# io_dac_convert.net
KiCad netlist of a schematic drawn in EAGLE
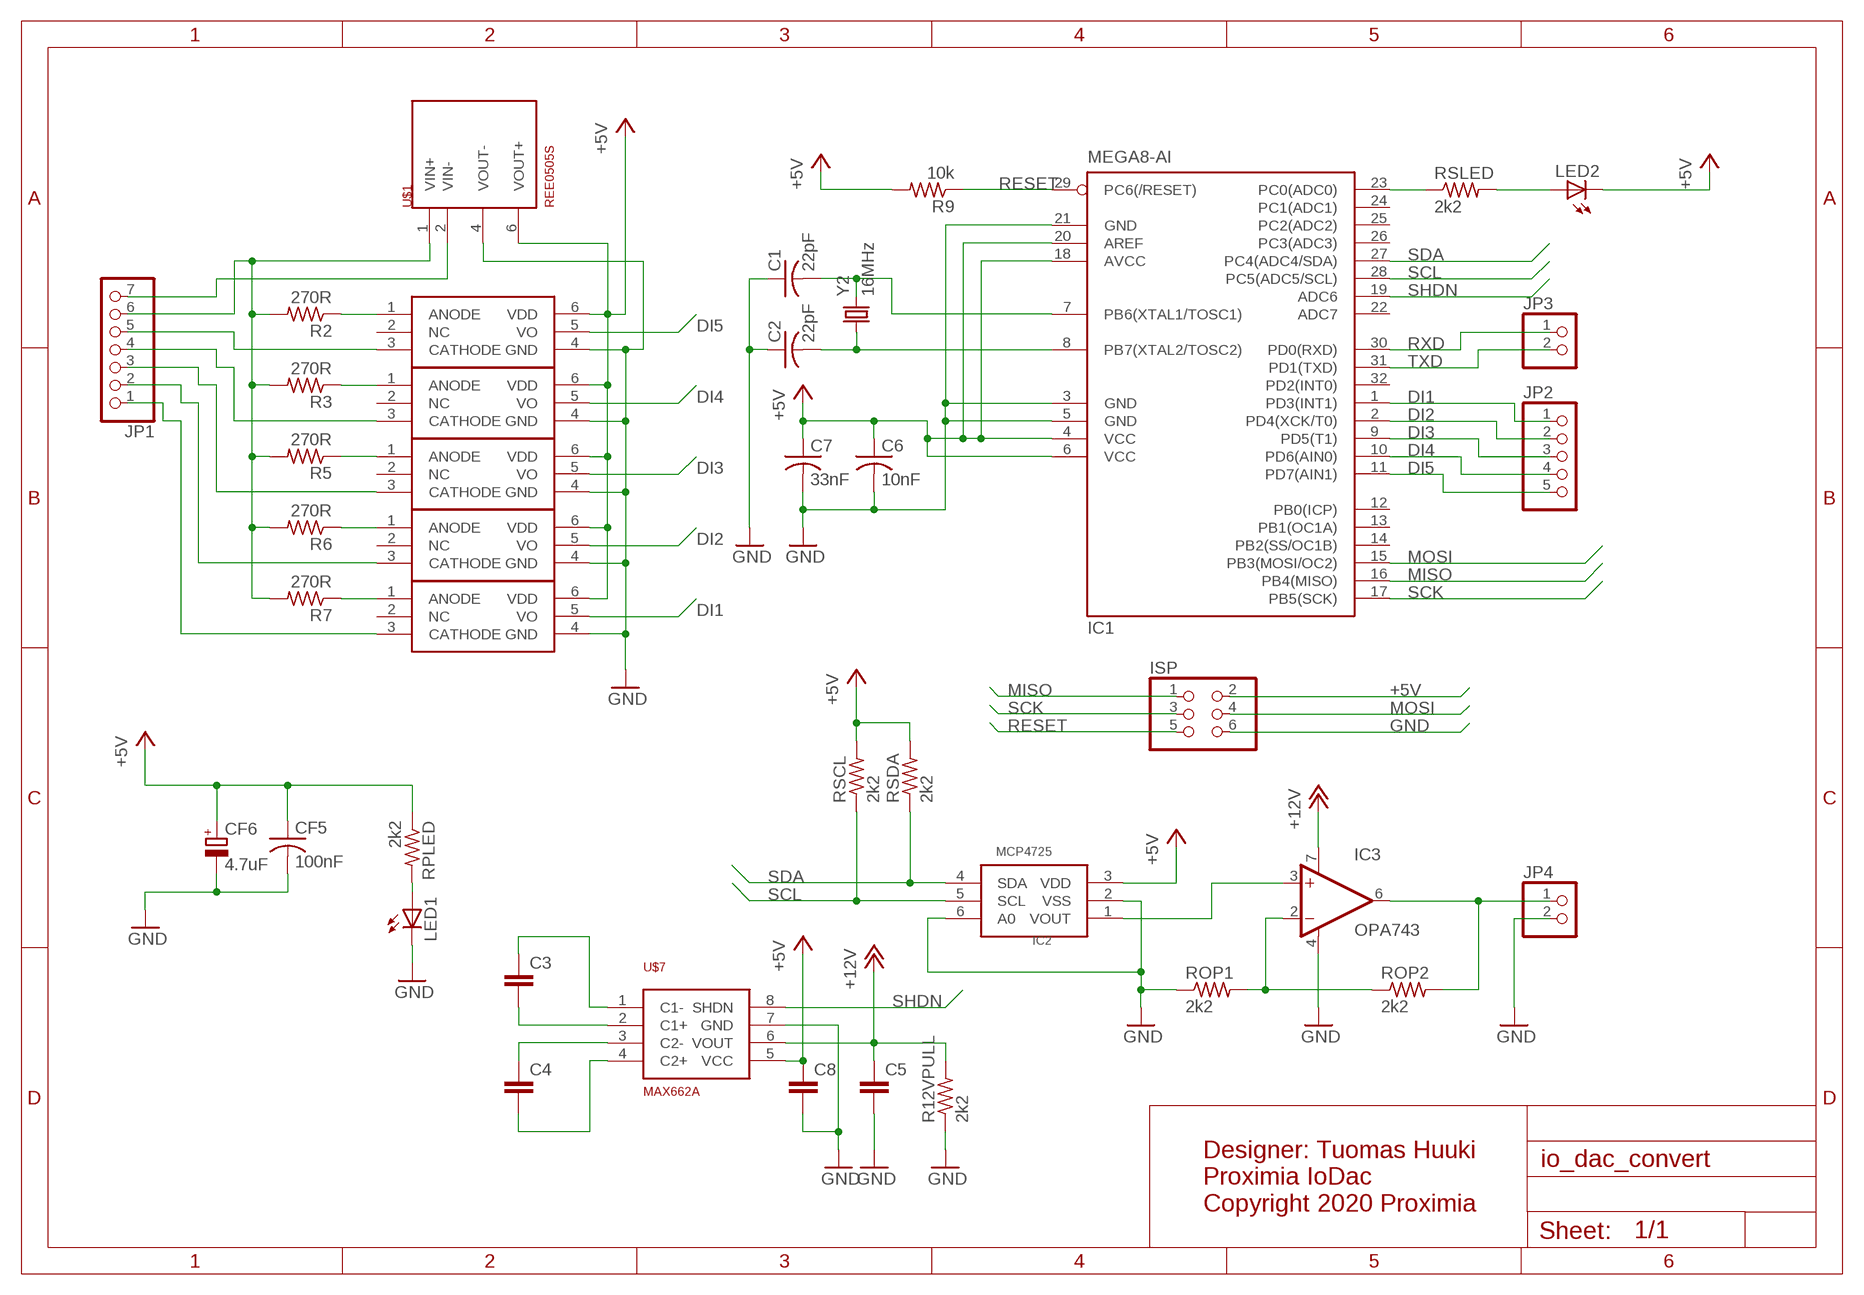
[diagram p0: schematic, sheet 1]

(export (version "E")
  (design (tool "Eeschema 10.0.6"))
  (components
    (comp (ref "C1")
      (value "22pF")
      (footprint "eagle-import:C0603")
      (libsource (lib "eagle-import") (part "C-USC0603"))
    )
    (comp (ref "C2")
      (value "22pF")
      (footprint "eagle-import:C0603")
      (libsource (lib "eagle-import") (part "C-USC0603"))
    )
    (comp (ref "C3")
      (value "C-EUC1206")
      (footprint "eagle-import:C1206")
      (libsource (lib "eagle-import") (part "C-EUC1206"))
    )
    (comp (ref "C4")
      (value "C-EUC1206")
      (footprint "eagle-import:C1206")
      (libsource (lib "eagle-import") (part "C-EUC1206"))
    )
    (comp (ref "C5")
      (value "C-EUC1206")
      (footprint "eagle-import:C1206")
      (libsource (lib "eagle-import") (part "C-EUC1206"))
    )
    (comp (ref "C6")
      (value "10nF")
      (footprint "eagle-import:C0603")
      (libsource (lib "eagle-import") (part "resistor_C-USC0603"))
    )
    (comp (ref "C7")
      (value "33nF")
      (footprint "eagle-import:C0603")
      (libsource (lib "eagle-import") (part "resistor_C-USC0603"))
    )
    (comp (ref "C8")
      (value "C-EUC1206")
      (footprint "eagle-import:C1206")
      (libsource (lib "eagle-import") (part "C-EUC1206"))
    )
    (comp (ref "CF5")
      (value "100nF")
      (footprint "eagle-import:C0603")
      (libsource (lib "eagle-import") (part "C-USC0603"))
    )
    (comp (ref "CF6")
      (value "4.7uF")
      (footprint "eagle-import:PANASONIC_B")
      (libsource (lib "eagle-import") (part "CPOL-EUB"))
    )
    (comp (ref "IC1")
      (value "MEGA8-AI")
      (footprint "eagle-import:TQFP32-08")
      (fields (field (name "MPN") "ATMEGA8-16AU"))
      (libsource (lib "eagle-import") (part "MEGA8-AI"))
    )
    (comp (ref "IC2")
      (value "MCP4725")
      (footprint "eagle-import:SOT23-6")
      (libsource (lib "eagle-import") (part "MCP4725"))
    )
    (comp (ref "IC3")
      (value "OPA743")
      (footprint "eagle-import:SO08")
      (fields (field (name "MPN") "AD8001ARZ"))
      (libsource (lib "eagle-import") (part "OPA658U"))
    )
    (comp (ref "ISP")
      (value "PINHD-2X3")
      (footprint "eagle-import:2X03")
      (libsource (lib "eagle-import") (part "PINHD-2X3"))
    )
    (comp (ref "JP1")
      (value "PINHD-1X7")
      (footprint "eagle-import:1X07")
      (libsource (lib "eagle-import") (part "PINHD-1X7"))
    )
    (comp (ref "JP2")
      (value "PINHD-1X5")
      (footprint "eagle-import:1X05")
      (libsource (lib "eagle-import") (part "PINHD-1X5"))
    )
    (comp (ref "JP3")
      (value "PINHD-1X2")
      (footprint "eagle-import:1X02")
      (libsource (lib "eagle-import") (part "PINHD-1X2"))
    )
    (comp (ref "JP4")
      (value "PINHD-1X2")
      (footprint "eagle-import:1X02")
      (libsource (lib "eagle-import") (part "PINHD-1X2"))
    )
    (comp (ref "LED1")
      (value "LEDSML1206")
      (footprint "eagle-import:SML1206")
      (libsource (lib "eagle-import") (part "LEDSML1206"))
    )
    (comp (ref "LED2")
      (value "LEDSML1206")
      (footprint "eagle-import:SML1206")
      (libsource (lib "eagle-import") (part "LEDSML1206"))
    )
    (comp (ref "R2")
      (value "270R")
      (footprint "eagle-import:R0603")
      (libsource (lib "eagle-import") (part "R-US_R0603"))
    )
    (comp (ref "R3")
      (value "270R")
      (footprint "eagle-import:R0603")
      (libsource (lib "eagle-import") (part "R-US_R0603"))
    )
    (comp (ref "R5")
      (value "270R")
      (footprint "eagle-import:R0603")
      (libsource (lib "eagle-import") (part "R-US_R0603"))
    )
    (comp (ref "R6")
      (value "270R")
      (footprint "eagle-import:R0603")
      (libsource (lib "eagle-import") (part "R-US_R0603"))
    )
    (comp (ref "R7")
      (value "270R")
      (footprint "eagle-import:R0603")
      (libsource (lib "eagle-import") (part "R-US_R0603"))
    )
    (comp (ref "R9")
      (value "10k")
      (footprint "eagle-import:R0603")
      (libsource (lib "eagle-import") (part "resistor_R-US_R0603"))
    )
    (comp (ref "R12VPULL")
      (value "2k2")
      (footprint "eagle-import:R0603")
      (libsource (lib "eagle-import") (part "R-US_R0603"))
    )
    (comp (ref "ROP1")
      (value "2k2")
      (footprint "eagle-import:R0603")
      (libsource (lib "eagle-import") (part "R-US_R0603"))
    )
    (comp (ref "ROP2")
      (value "2k2")
      (footprint "eagle-import:R0603")
      (libsource (lib "eagle-import") (part "R-US_R0603"))
    )
    (comp (ref "RPLED")
      (value "2k2")
      (footprint "eagle-import:R0603")
      (libsource (lib "eagle-import") (part "R-US_R0603"))
    )
    (comp (ref "RSCL")
      (value "2k2")
      (footprint "eagle-import:R0603")
      (libsource (lib "eagle-import") (part "R-US_R0603"))
    )
    (comp (ref "RSDA")
      (value "2k2")
      (footprint "eagle-import:R0603")
      (libsource (lib "eagle-import") (part "R-US_R0603"))
    )
    (comp (ref "RSLED")
      (value "2k2")
      (footprint "eagle-import:R0603")
      (libsource (lib "eagle-import") (part "R-US_R0603"))
    )
    (comp (ref "U$1")
      (value "REE0505S")
      (footprint "eagle-import:SIP-6")
      (libsource (lib "eagle-import") (part "REE0505S"))
    )
    (comp (ref "U$2")
      (value "SI8710")
      (footprint "eagle-import:SDIP-6")
      (libsource (lib "eagle-import") (part "SI8710"))
    )
    (comp (ref "U$3")
      (value "SI8710")
      (footprint "eagle-import:SDIP-6")
      (libsource (lib "eagle-import") (part "SI8710"))
    )
    (comp (ref "U$4")
      (value "SI8710")
      (footprint "eagle-import:SDIP-6")
      (libsource (lib "eagle-import") (part "SI8710"))
    )
    (comp (ref "U$5")
      (value "SI8710")
      (footprint "eagle-import:SDIP-6")
      (libsource (lib "eagle-import") (part "SI8710"))
    )
    (comp (ref "U$6")
      (value "SI8710")
      (footprint "eagle-import:SDIP-6")
      (libsource (lib "eagle-import") (part "SI8710"))
    )
    (comp (ref "U$7")
      (value "MAX662A")
      (footprint "eagle-import:SO8")
      (libsource (lib "eagle-import") (part "MAX662A"))
    )
    (comp (ref "Y2")
      (value "16MHz")
      (footprint "eagle-import:CRYSTAL-SMD-5X3")
      (libsource (lib "eagle-import") (part "CRYSTAL5X3"))
    )
  )
  (nets
    (net (code "1") (name "+5V") (class "Default")
      (node (ref "C6") (pin "1") (pinfunction "1_1") (pintype "passive"))
      (node (ref "C7") (pin "1") (pinfunction "1_1") (pintype "passive"))
      (node (ref "C8") (pin "1") (pinfunction "1_1") (pintype "passive"))
      (node (ref "CF5") (pin "1") (pinfunction "1_1") (pintype "passive"))
      (node (ref "CF6") (pin "+") (pinfunction "+_+") (pintype "passive"))
      (node (ref "IC1") (pin "18") (pinfunction "AVCC_18") (pintype "power_in"))
      (node (ref "IC1") (pin "20") (pinfunction "AREF_20") (pintype "passive"))
      (node (ref "IC1") (pin "4") (pinfunction "VCC_4") (pintype "power_in"))
      (node (ref "IC1") (pin "6") (pinfunction "VCC_6") (pintype "power_in"))
      (node (ref "IC2") (pin "3") (pinfunction "VDD_3") (pintype "bidirectional"))
      (node (ref "ISP") (pin "2") (pinfunction "2_2") (pintype "passive"))
      (node (ref "LED2") (pin "C") (pinfunction "C_C") (pintype "passive"))
      (node (ref "R9") (pin "2") (pinfunction "2_2") (pintype "passive"))
      (node (ref "RPLED") (pin "1") (pinfunction "1_1") (pintype "passive"))
      (node (ref "RSCL") (pin "2") (pinfunction "2_2") (pintype "passive"))
      (node (ref "RSDA") (pin "2") (pinfunction "2_2") (pintype "passive"))
      (node (ref "U$1") (pin "6") (pinfunction "VOUT+_6") (pintype "bidirectional"))
      (node (ref "U$2") (pin "6") (pinfunction "VDD_6") (pintype "bidirectional"))
      (node (ref "U$3") (pin "6") (pinfunction "VDD_6") (pintype "bidirectional"))
      (node (ref "U$4") (pin "6") (pinfunction "VDD_6") (pintype "bidirectional"))
      (node (ref "U$5") (pin "6") (pinfunction "VDD_6") (pintype "bidirectional"))
      (node (ref "U$6") (pin "6") (pinfunction "VDD_6") (pintype "bidirectional"))
      (node (ref "U$7") (pin "5") (pinfunction "VCC_5") (pintype "bidirectional"))
    )
    (net (code "2") (name "+12V") (class "Default")
      (node (ref "C5") (pin "1") (pinfunction "1_1") (pintype "passive"))
      (node (ref "IC3") (pin "7") (pinfunction "V+_7") (pintype "power_in"))
      (node (ref "R12VPULL") (pin "2") (pinfunction "2_2") (pintype "passive"))
      (node (ref "U$7") (pin "6") (pinfunction "VOUT_6") (pintype "bidirectional"))
    )
    (net (code "3") (name "/DI1") (class "Default")
      (node (ref "IC1") (pin "1") (pinfunction "PD3(INT1)_1") (pintype "bidirectional"))
      (node (ref "JP2") (pin "1") (pinfunction "1_1") (pintype "passive"))
      (node (ref "U$6") (pin "5") (pinfunction "VO_5") (pintype "bidirectional"))
    )
    (net (code "4") (name "/DI2") (class "Default")
      (node (ref "IC1") (pin "2") (pinfunction "PD4(XCK/T0)_2") (pintype "bidirectional"))
      (node (ref "JP2") (pin "2") (pinfunction "2_2") (pintype "passive"))
      (node (ref "U$5") (pin "5") (pinfunction "VO_5") (pintype "bidirectional"))
    )
    (net (code "5") (name "/DI3") (class "Default")
      (node (ref "IC1") (pin "9") (pinfunction "PD5(T1)_9") (pintype "bidirectional"))
      (node (ref "JP2") (pin "3") (pinfunction "3_3") (pintype "passive"))
      (node (ref "U$4") (pin "5") (pinfunction "VO_5") (pintype "bidirectional"))
    )
    (net (code "6") (name "/DI4") (class "Default")
      (node (ref "IC1") (pin "10") (pinfunction "PD6(AIN0)_10") (pintype "bidirectional"))
      (node (ref "JP2") (pin "4") (pinfunction "4_4") (pintype "passive"))
      (node (ref "U$3") (pin "5") (pinfunction "VO_5") (pintype "bidirectional"))
    )
    (net (code "7") (name "/DI5") (class "Default")
      (node (ref "IC1") (pin "11") (pinfunction "PD7(AIN1)_11") (pintype "bidirectional"))
      (node (ref "JP2") (pin "5") (pinfunction "5_5") (pintype "passive"))
      (node (ref "U$2") (pin "5") (pinfunction "VO_5") (pintype "bidirectional"))
    )
    (net (code "8") (name "/MISO") (class "Default")
      (node (ref "IC1") (pin "16") (pinfunction "PB4(MISO)_16") (pintype "bidirectional"))
      (node (ref "ISP") (pin "1") (pinfunction "1_1") (pintype "passive"))
    )
    (net (code "9") (name "/MOSI") (class "Default")
      (node (ref "IC1") (pin "15") (pinfunction "PB3(MOSI/OC2)_15") (pintype "bidirectional"))
      (node (ref "ISP") (pin "4") (pinfunction "4_4") (pintype "passive"))
    )
    (net (code "10") (name "/RESET") (class "Default")
      (node (ref "IC1") (pin "29") (pinfunction "PC6(/RESET)_29") (pintype "bidirectional"))
      (node (ref "ISP") (pin "5") (pinfunction "5_5") (pintype "passive"))
      (node (ref "R9") (pin "1") (pinfunction "1_1") (pintype "passive"))
    )
    (net (code "11") (name "/RXD") (class "Default")
      (node (ref "IC1") (pin "30") (pinfunction "PD0(RXD)_30") (pintype "bidirectional"))
      (node (ref "JP3") (pin "1") (pinfunction "1_1") (pintype "passive"))
    )
    (net (code "12") (name "/SCK") (class "Default")
      (node (ref "IC1") (pin "17") (pinfunction "PB5(SCK)_17") (pintype "bidirectional"))
      (node (ref "ISP") (pin "3") (pinfunction "3_3") (pintype "passive"))
    )
    (net (code "13") (name "/SCL") (class "Default")
      (node (ref "IC1") (pin "28") (pinfunction "PC5(ADC5/SCL)_28") (pintype "bidirectional"))
      (node (ref "IC2") (pin "5") (pinfunction "SCL_5") (pintype "bidirectional"))
      (node (ref "RSCL") (pin "1") (pinfunction "1_1") (pintype "passive"))
    )
    (net (code "14") (name "/SDA") (class "Default")
      (node (ref "IC1") (pin "27") (pinfunction "PC4(ADC4/SDA)_27") (pintype "bidirectional"))
      (node (ref "IC2") (pin "4") (pinfunction "SDA_4") (pintype "bidirectional"))
      (node (ref "RSDA") (pin "1") (pinfunction "1_1") (pintype "passive"))
    )
    (net (code "15") (name "/SHDN") (class "Default")
      (node (ref "IC1") (pin "19") (pinfunction "ADC6_19") (pintype "bidirectional"))
      (node (ref "U$7") (pin "8") (pinfunction "SHDN_8") (pintype "bidirectional"))
    )
    (net (code "16") (name "/TXD") (class "Default")
      (node (ref "IC1") (pin "31") (pinfunction "PD1(TXD)_31") (pintype "bidirectional"))
      (node (ref "JP3") (pin "2") (pinfunction "2_2") (pintype "passive"))
    )
    (net (code "17") (name "GND") (class "Default")
      (node (ref "C1") (pin "1") (pinfunction "1_1") (pintype "passive"))
      (node (ref "C2") (pin "1") (pinfunction "1_1") (pintype "passive"))
      (node (ref "C5") (pin "2") (pinfunction "2_2") (pintype "passive"))
      (node (ref "C6") (pin "2") (pinfunction "2_2") (pintype "passive"))
      (node (ref "C7") (pin "2") (pinfunction "2_2") (pintype "passive"))
      (node (ref "C8") (pin "2") (pinfunction "2_2") (pintype "passive"))
      (node (ref "CF5") (pin "2") (pinfunction "2_2") (pintype "passive"))
      (node (ref "CF6") (pin "-") (pinfunction "-_-") (pintype "passive"))
      (node (ref "IC1") (pin "21") (pinfunction "GND_21") (pintype "power_in"))
      (node (ref "IC1") (pin "3") (pinfunction "GND_3") (pintype "power_in"))
      (node (ref "IC1") (pin "5") (pinfunction "GND_5") (pintype "power_in"))
      (node (ref "IC2") (pin "2") (pinfunction "VSS_2") (pintype "bidirectional"))
      (node (ref "IC2") (pin "6") (pinfunction "A0_6") (pintype "bidirectional"))
      (node (ref "IC3") (pin "4") (pinfunction "V-_4") (pintype "power_in"))
      (node (ref "ISP") (pin "6") (pinfunction "6_6") (pintype "passive"))
      (node (ref "JP4") (pin "2") (pinfunction "2_2") (pintype "passive"))
      (node (ref "LED1") (pin "C") (pinfunction "C_C") (pintype "passive"))
      (node (ref "R12VPULL") (pin "1") (pinfunction "1_1") (pintype "passive"))
      (node (ref "ROP1") (pin "1") (pinfunction "1_1") (pintype "passive"))
      (node (ref "U$1") (pin "4") (pinfunction "VOUT-_4") (pintype "bidirectional"))
      (node (ref "U$2") (pin "4") (pinfunction "GND_4") (pintype "bidirectional"))
      (node (ref "U$3") (pin "4") (pinfunction "GND_4") (pintype "bidirectional"))
      (node (ref "U$4") (pin "4") (pinfunction "GND_4") (pintype "bidirectional"))
      (node (ref "U$5") (pin "4") (pinfunction "GND_4") (pintype "bidirectional"))
      (node (ref "U$6") (pin "4") (pinfunction "GND_4") (pintype "bidirectional"))
      (node (ref "U$7") (pin "7") (pinfunction "GND_7") (pintype "bidirectional"))
    )
    (net (code "18") (name "Net-(IC1-PB6(XTAL1{slash}TOSC1))") (class "Default")
      (node (ref "C1") (pin "2") (pinfunction "2_2") (pintype "passive"))
      (node (ref "IC1") (pin "7") (pinfunction "PB6(XTAL1/TOSC1)_7") (pintype "bidirectional"))
      (node (ref "Y2") (pin "3") (pinfunction "2_3") (pintype "passive"))
    )
    (net (code "19") (name "Net-(IC1-PB7(XTAL2{slash}TOSC2))") (class "Default")
      (node (ref "C2") (pin "2") (pinfunction "2_2") (pintype "passive"))
      (node (ref "IC1") (pin "8") (pinfunction "PB7(XTAL2/TOSC2)_8") (pintype "bidirectional"))
      (node (ref "Y2") (pin "1") (pinfunction "1_1") (pintype "passive"))
    )
    (net (code "20") (name "Net-(IC1-PC0(ADC0))") (class "Default")
      (node (ref "IC1") (pin "23") (pinfunction "PC0(ADC0)_23") (pintype "bidirectional"))
      (node (ref "RSLED") (pin "1") (pinfunction "1_1") (pintype "passive"))
    )
    (net (code "21") (name "Net-(IC2-VOUT)") (class "Default")
      (node (ref "IC2") (pin "1") (pinfunction "VOUT_1") (pintype "bidirectional"))
      (node (ref "IC3") (pin "3") (pinfunction "+IN_3") (pintype "input"))
    )
    (net (code "22") (name "Net-(IC3--IN)") (class "Default")
      (node (ref "IC3") (pin "2") (pinfunction "-IN_2") (pintype "input"))
      (node (ref "ROP1") (pin "2") (pinfunction "2_2") (pintype "passive"))
      (node (ref "ROP2") (pin "1") (pinfunction "1_1") (pintype "passive"))
    )
    (net (code "23") (name "Net-(IC3-OUT)") (class "Default")
      (node (ref "IC3") (pin "6") (pinfunction "OUT_6") (pintype "output"))
      (node (ref "JP4") (pin "1") (pinfunction "1_1") (pintype "passive"))
      (node (ref "ROP2") (pin "2") (pinfunction "2_2") (pintype "passive"))
    )
    (net (code "24") (name "Net-(LED1-PadA)") (class "Default")
      (node (ref "LED1") (pin "A") (pinfunction "A_A") (pintype "passive"))
      (node (ref "RPLED") (pin "2") (pinfunction "2_2") (pintype "passive"))
    )
    (net (code "25") (name "Net-(LED2-PadA)") (class "Default")
      (node (ref "LED2") (pin "A") (pinfunction "A_A") (pintype "passive"))
      (node (ref "RSLED") (pin "2") (pinfunction "2_2") (pintype "passive"))
    )
    (net (code "26") (name "Net-(U$1-VIN+)") (class "Default")
      (node (ref "JP1") (pin "6") (pinfunction "6_6") (pintype "passive"))
      (node (ref "R2") (pin "2") (pinfunction "2_2") (pintype "passive"))
      (node (ref "R3") (pin "2") (pinfunction "2_2") (pintype "passive"))
      (node (ref "R5") (pin "2") (pinfunction "2_2") (pintype "passive"))
      (node (ref "R6") (pin "2") (pinfunction "2_2") (pintype "passive"))
      (node (ref "R7") (pin "2") (pinfunction "2_2") (pintype "passive"))
      (node (ref "U$1") (pin "1") (pinfunction "VIN+_1") (pintype "bidirectional"))
    )
    (net (code "27") (name "Net-(U$1-VIN-)") (class "Default")
      (node (ref "JP1") (pin "7") (pinfunction "7_7") (pintype "passive"))
      (node (ref "U$1") (pin "2") (pinfunction "VIN-_2") (pintype "bidirectional"))
    )
    (net (code "28") (name "Net-(U$2-ANODE)") (class "Default")
      (node (ref "R2") (pin "1") (pinfunction "1_1") (pintype "passive"))
      (node (ref "U$2") (pin "1") (pinfunction "ANODE_1") (pintype "bidirectional"))
    )
    (net (code "29") (name "Net-(U$2-CATHODE)") (class "Default")
      (node (ref "JP1") (pin "5") (pinfunction "5_5") (pintype "passive"))
      (node (ref "U$2") (pin "3") (pinfunction "CATHODE_3") (pintype "bidirectional"))
    )
    (net (code "30") (name "Net-(U$3-ANODE)") (class "Default")
      (node (ref "R3") (pin "1") (pinfunction "1_1") (pintype "passive"))
      (node (ref "U$3") (pin "1") (pinfunction "ANODE_1") (pintype "bidirectional"))
    )
    (net (code "31") (name "Net-(U$3-CATHODE)") (class "Default")
      (node (ref "JP1") (pin "4") (pinfunction "4_4") (pintype "passive"))
      (node (ref "U$3") (pin "3") (pinfunction "CATHODE_3") (pintype "bidirectional"))
    )
    (net (code "32") (name "Net-(U$4-ANODE)") (class "Default")
      (node (ref "R5") (pin "1") (pinfunction "1_1") (pintype "passive"))
      (node (ref "U$4") (pin "1") (pinfunction "ANODE_1") (pintype "bidirectional"))
    )
    (net (code "33") (name "Net-(U$4-CATHODE)") (class "Default")
      (node (ref "JP1") (pin "3") (pinfunction "3_3") (pintype "passive"))
      (node (ref "U$4") (pin "3") (pinfunction "CATHODE_3") (pintype "bidirectional"))
    )
    (net (code "34") (name "Net-(U$5-ANODE)") (class "Default")
      (node (ref "R6") (pin "1") (pinfunction "1_1") (pintype "passive"))
      (node (ref "U$5") (pin "1") (pinfunction "ANODE_1") (pintype "bidirectional"))
    )
    (net (code "35") (name "Net-(U$5-CATHODE)") (class "Default")
      (node (ref "JP1") (pin "2") (pinfunction "2_2") (pintype "passive"))
      (node (ref "U$5") (pin "3") (pinfunction "CATHODE_3") (pintype "bidirectional"))
    )
    (net (code "36") (name "Net-(U$6-ANODE)") (class "Default")
      (node (ref "R7") (pin "1") (pinfunction "1_1") (pintype "passive"))
      (node (ref "U$6") (pin "1") (pinfunction "ANODE_1") (pintype "bidirectional"))
    )
    (net (code "37") (name "Net-(U$6-CATHODE)") (class "Default")
      (node (ref "JP1") (pin "1") (pinfunction "1_1") (pintype "passive"))
      (node (ref "U$6") (pin "3") (pinfunction "CATHODE_3") (pintype "bidirectional"))
    )
    (net (code "38") (name "Net-(U$7-C1+)") (class "Default")
      (node (ref "C3") (pin "2") (pinfunction "2_2") (pintype "passive"))
      (node (ref "U$7") (pin "2") (pinfunction "C1+_2") (pintype "bidirectional"))
    )
    (net (code "39") (name "Net-(U$7-C1-)") (class "Default")
      (node (ref "C3") (pin "1") (pinfunction "1_1") (pintype "passive"))
      (node (ref "U$7") (pin "1") (pinfunction "C1-_1") (pintype "bidirectional"))
    )
    (net (code "40") (name "Net-(U$7-C2+)") (class "Default")
      (node (ref "C4") (pin "2") (pinfunction "2_2") (pintype "passive"))
      (node (ref "U$7") (pin "4") (pinfunction "C2+_4") (pintype "bidirectional"))
    )
    (net (code "41") (name "Net-(U$7-C2-)") (class "Default")
      (node (ref "C4") (pin "1") (pinfunction "1_1") (pintype "passive"))
      (node (ref "U$7") (pin "3") (pinfunction "C2-_3") (pintype "bidirectional"))
    )
    (net (code "42") (name "unconnected-(IC1-ADC7-Pad22)") (class "Default")
      (node (ref "IC1") (pin "22") (pinfunction "ADC7_22") (pintype "bidirectional"))
    )
    (net (code "43") (name "unconnected-(IC1-PB0(ICP)-Pad12)") (class "Default")
      (node (ref "IC1") (pin "12") (pinfunction "PB0(ICP)_12") (pintype "bidirectional"))
    )
    (net (code "44") (name "unconnected-(IC1-PB1(OC1A)-Pad13)") (class "Default")
      (node (ref "IC1") (pin "13") (pinfunction "PB1(OC1A)_13") (pintype "bidirectional"))
    )
    (net (code "45") (name "unconnected-(IC1-PB2(SS{slash}OC1B)-Pad14)") (class "Default")
      (node (ref "IC1") (pin "14") (pinfunction "PB2(SS/OC1B)_14") (pintype "bidirectional"))
    )
    (net (code "46") (name "unconnected-(IC1-PC1(ADC1)-Pad24)") (class "Default")
      (node (ref "IC1") (pin "24") (pinfunction "PC1(ADC1)_24") (pintype "bidirectional"))
    )
    (net (code "47") (name "unconnected-(IC1-PC2(ADC2)-Pad25)") (class "Default")
      (node (ref "IC1") (pin "25") (pinfunction "PC2(ADC2)_25") (pintype "bidirectional"))
    )
    (net (code "48") (name "unconnected-(IC1-PC3(ADC3)-Pad26)") (class "Default")
      (node (ref "IC1") (pin "26") (pinfunction "PC3(ADC3)_26") (pintype "bidirectional"))
    )
    (net (code "49") (name "unconnected-(IC1-PD2(INT0)-Pad32)") (class "Default")
      (node (ref "IC1") (pin "32") (pinfunction "PD2(INT0)_32") (pintype "bidirectional"))
    )
    (net (code "50") (name "unconnected-(U$2-NC-Pad2)") (class "Default")
      (node (ref "U$2") (pin "2") (pinfunction "NC_2") (pintype "bidirectional"))
    )
    (net (code "51") (name "unconnected-(U$3-NC-Pad2)") (class "Default")
      (node (ref "U$3") (pin "2") (pinfunction "NC_2") (pintype "bidirectional"))
    )
    (net (code "52") (name "unconnected-(U$4-NC-Pad2)") (class "Default")
      (node (ref "U$4") (pin "2") (pinfunction "NC_2") (pintype "bidirectional"))
    )
    (net (code "53") (name "unconnected-(U$5-NC-Pad2)") (class "Default")
      (node (ref "U$5") (pin "2") (pinfunction "NC_2") (pintype "bidirectional"))
    )
    (net (code "54") (name "unconnected-(U$6-NC-Pad2)") (class "Default")
      (node (ref "U$6") (pin "2") (pinfunction "NC_2") (pintype "bidirectional"))
    )
  )
)
